# Nucleo_DCO_PSU.net
KiCad netlist of a schematic drawn in EAGLE
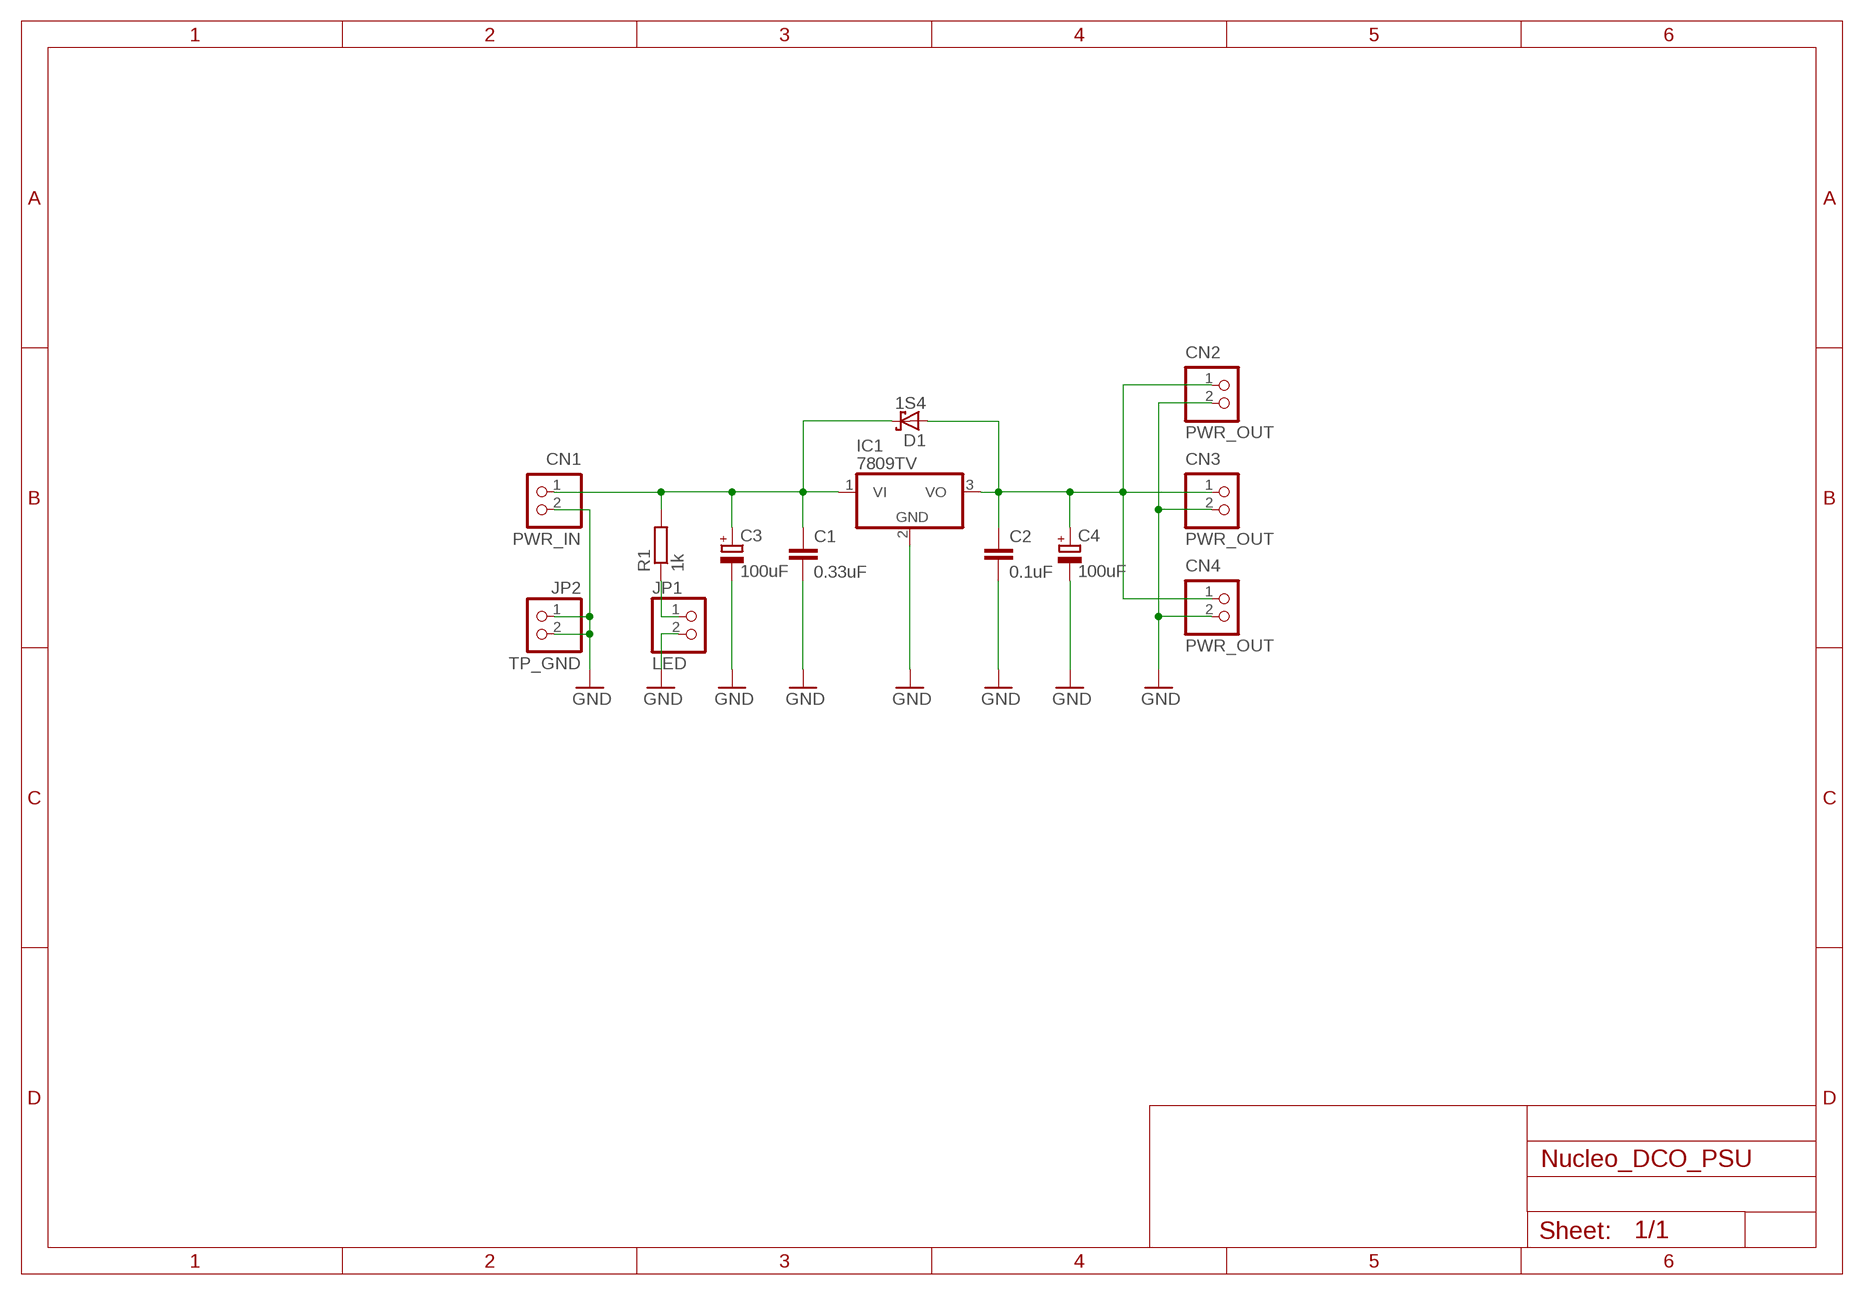
[diagram p0: schematic, sheet 1]

(export (version "E")
  (design (tool "Eeschema 10.0.6"))
  (components
    (comp (ref "C1")
      (value "0.33uF")
      (footprint "eagle-import:C025-024X044")
      (libsource (lib "eagle-import") (part "C-EU025-024X044"))
    )
    (comp (ref "C2")
      (value "0.1uF")
      (footprint "eagle-import:C025-024X044")
      (libsource (lib "eagle-import") (part "C-EU025-024X044"))
    )
    (comp (ref "C3")
      (value "100uF")
      (footprint "eagle-import:E5-8,5")
      (libsource (lib "eagle-import") (part "CPOL-EUE5-8.5"))
    )
    (comp (ref "C4")
      (value "100uF")
      (footprint "eagle-import:E5-8,5")
      (libsource (lib "eagle-import") (part "CPOL-EUE5-8.5"))
    )
    (comp (ref "CN1")
      (value "PWR_IN")
      (footprint "eagle-import:B2B-XH-A")
      (libsource (lib "eagle-import") (part "B2B-XH-A"))
    )
    (comp (ref "CN2")
      (value "PWR_OUT")
      (footprint "eagle-import:B2B-XH-A")
      (libsource (lib "eagle-import") (part "B2B-XH-A"))
    )
    (comp (ref "CN3")
      (value "PWR_OUT")
      (footprint "eagle-import:B2B-XH-A")
      (libsource (lib "eagle-import") (part "B2B-XH-A"))
    )
    (comp (ref "CN4")
      (value "PWR_OUT")
      (footprint "eagle-import:B2B-XH-A")
      (libsource (lib "eagle-import") (part "B2B-XH-A"))
    )
    (comp (ref "D1")
      (value "1S4")
      (footprint "eagle-import:DO35-7")
      (libsource (lib "eagle-import") (part "SCHOTTKY-DIODEDO35-7"))
    )
    (comp (ref "IC1")
      (value "7809TV")
      (footprint "eagle-import:TO220V")
      (libsource (lib "eagle-import") (part "78TV12"))
    )
    (comp (ref "JP1")
      (value "LED")
      (footprint "eagle-import:1X02")
      (libsource (lib "eagle-import") (part "PINHD-1X2"))
    )
    (comp (ref "JP2")
      (value "TP_GND")
      (footprint "eagle-import:1X02")
      (libsource (lib "eagle-import") (part "PINHD-1X2"))
    )
    (comp (ref "R1")
      (value "1k")
      (footprint "eagle-import:0207_7")
      (libsource (lib "eagle-import") (part "R-EU_0207/7"))
    )
  )
  (nets
    (net (code "1") (name "GND") (class "Default")
      (node (ref "C1") (pin "2") (pinfunction "2_2") (pintype "passive"))
      (node (ref "C2") (pin "2") (pinfunction "2_2") (pintype "passive"))
      (node (ref "C3") (pin "-") (pinfunction "-_-") (pintype "passive"))
      (node (ref "C4") (pin "-") (pinfunction "-_-") (pintype "passive"))
      (node (ref "CN1") (pin "2") (pinfunction "2_2") (pintype "passive"))
      (node (ref "CN2") (pin "2") (pinfunction "2_2") (pintype "passive"))
      (node (ref "CN3") (pin "2") (pinfunction "2_2") (pintype "passive"))
      (node (ref "CN4") (pin "2") (pinfunction "2_2") (pintype "passive"))
      (node (ref "IC1") (pin "2") (pinfunction "GND_2") (pintype "passive"))
      (node (ref "JP1") (pin "2") (pinfunction "2_2") (pintype "passive"))
      (node (ref "JP2") (pin "1") (pinfunction "1_1") (pintype "passive"))
      (node (ref "JP2") (pin "2") (pinfunction "2_2") (pintype "passive"))
    )
    (net (code "2") (name "Net-(IC1-VI)") (class "Default")
      (node (ref "C1") (pin "1") (pinfunction "1_1") (pintype "passive"))
      (node (ref "C3") (pin "+") (pinfunction "+_+") (pintype "passive"))
      (node (ref "CN1") (pin "1") (pinfunction "1_1") (pintype "passive"))
      (node (ref "D1") (pin "C") (pinfunction "C_C") (pintype "passive"))
      (node (ref "IC1") (pin "1") (pinfunction "VI_1") (pintype "input"))
      (node (ref "R1") (pin "2") (pinfunction "2_2") (pintype "passive"))
    )
    (net (code "3") (name "Net-(IC1-VO)") (class "Default")
      (node (ref "C2") (pin "1") (pinfunction "1_1") (pintype "passive"))
      (node (ref "C4") (pin "+") (pinfunction "+_+") (pintype "passive"))
      (node (ref "CN2") (pin "1") (pinfunction "1_1") (pintype "passive"))
      (node (ref "CN3") (pin "1") (pinfunction "1_1") (pintype "passive"))
      (node (ref "CN4") (pin "1") (pinfunction "1_1") (pintype "passive"))
      (node (ref "D1") (pin "A") (pinfunction "A_A") (pintype "passive"))
      (node (ref "IC1") (pin "3") (pinfunction "VO_3") (pintype "passive"))
    )
    (net (code "4") (name "Net-(JP1-Pad1)") (class "Default")
      (node (ref "JP1") (pin "1") (pinfunction "1_1") (pintype "passive"))
      (node (ref "R1") (pin "1") (pinfunction "1_1") (pintype "passive"))
    )
  )
)
